# HDMI_out.net
KiCad netlist of a schematic drawn in Altium Designer
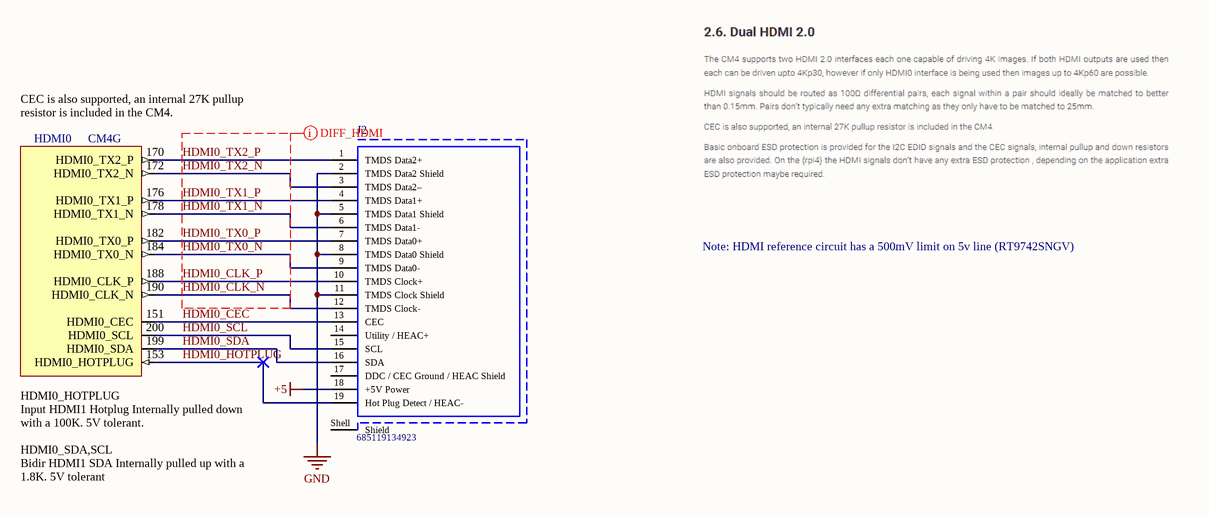
[diagram p0: HDMI out.SchDoc]

(export (version "E")
  (design (tool "Eeschema 10.0.6"))
  (components
    (comp (ref "CM4")
      (value "Raspberry Pi Compute Module 4")
      (footprint "CM4-F40C-100DS-0.4v_1.5mm_0mm")
      (description "Raspberry Pi Compute Module 4 by Amornthep Phunsin")
      (libsource (lib "CM4") (part "CM4"))
    )
    (comp (ref "J2")
      (value "685119134923")
      (footprint "685119134923")
      (description "HDMI Type A Receptacle WR-HDMI, Horizontal, SMT")
      (fields (field (name "MANUFACTURER") "Wurth Elektronik") (field (name "PUBLISHER") "WurthElektronik"))
      (libsource (lib "Altium Content Vault") (part "WE-CN-1P-1F-HD19"))
    )
  )
  (nets
    (net (code "1") (name "+5") (class "Default")
      (node (ref "J2") (pin "18") (pinfunction "+5V_Power_18") (pintype "passive"))
    )
    (net (code "2") (name "/HDMI0_CEC") (class "Default")
      (node (ref "CM4") (pin "151") (pinfunction "HDMI0_CEC_151") (pintype "open_collector"))
      (node (ref "J2") (pin "13") (pinfunction "CEC_13") (pintype "passive"))
    )
    (net (code "3") (name "/HDMI0_CLK_N") (class "Default")
      (node (ref "CM4") (pin "190") (pinfunction "HDMI0_CLK_N_190") (pintype "output"))
      (node (ref "J2") (pin "12") (pinfunction "TMDS_Clock-_12") (pintype "passive"))
    )
    (net (code "4") (name "/HDMI0_CLK_P") (class "Default")
      (node (ref "CM4") (pin "188") (pinfunction "HDMI0_CLK_P_188") (pintype "output"))
      (node (ref "J2") (pin "10") (pinfunction "TMDS_Clock+_10") (pintype "passive"))
    )
    (net (code "5") (name "/HDMI0_HOTPLUG") (class "Default")
      (node (ref "CM4") (pin "153") (pinfunction "HDMI0_HOTPLUG_153") (pintype "input"))
      (node (ref "J2") (pin "19") (pinfunction "Hot_Plug_Detect_/_HEAC-_19") (pintype "passive"))
    )
    (net (code "6") (name "/HDMI0_SCL") (class "Default")
      (node (ref "CM4") (pin "200") (pinfunction "HDMI0_SCL_200") (pintype "open_collector"))
      (node (ref "J2") (pin "15") (pinfunction "SCL_15") (pintype "passive"))
    )
    (net (code "7") (name "/HDMI0_SDA") (class "Default")
      (node (ref "CM4") (pin "199") (pinfunction "HDMI0_SDA_199") (pintype "bidirectional"))
      (node (ref "J2") (pin "16") (pinfunction "SDA_16") (pintype "passive"))
    )
    (net (code "8") (name "/HDMI0_TX0_N") (class "Default")
      (node (ref "CM4") (pin "184") (pinfunction "HDMI0_TX0_N_184") (pintype "output"))
      (node (ref "J2") (pin "9") (pinfunction "TMDS_Data0-_9") (pintype "passive"))
    )
    (net (code "9") (name "/HDMI0_TX0_P") (class "Default")
      (node (ref "CM4") (pin "182") (pinfunction "HDMI0_TX0_P_182") (pintype "output"))
      (node (ref "J2") (pin "7") (pinfunction "TMDS_Data0+_7") (pintype "passive"))
    )
    (net (code "10") (name "/HDMI0_TX1_N") (class "Default")
      (node (ref "CM4") (pin "178") (pinfunction "HDMI0_TX1_N_178") (pintype "output"))
      (node (ref "J2") (pin "6") (pinfunction "TMDS_Data1-_6") (pintype "passive"))
    )
    (net (code "11") (name "/HDMI0_TX1_P") (class "Default")
      (node (ref "CM4") (pin "176") (pinfunction "HDMI0_TX1_P_176") (pintype "output"))
      (node (ref "J2") (pin "4") (pinfunction "TMDS_Data1+_4") (pintype "passive"))
    )
    (net (code "12") (name "/HDMI0_TX2_N") (class "Default")
      (node (ref "CM4") (pin "172") (pinfunction "HDMI0_TX2_N_172") (pintype "output"))
      (node (ref "J2") (pin "3") (pinfunction "TMDS_Data2–_3") (pintype "passive"))
    )
    (net (code "13") (name "/HDMI0_TX2_P") (class "Default")
      (node (ref "CM4") (pin "170") (pinfunction "HDMI0_TX2_P_170") (pintype "output"))
      (node (ref "J2") (pin "1") (pinfunction "TMDS_Data2+_1") (pintype "passive"))
    )
    (net (code "14") (name "GND") (class "Default")
      (node (ref "J2") (pin "11") (pinfunction "TMDS_Clock_Shield_11") (pintype "passive"))
      (node (ref "J2") (pin "2") (pinfunction "TMDS_Data2_Shield_2") (pintype "passive"))
      (node (ref "J2") (pin "5") (pinfunction "TMDS_Data1_Shield_5") (pintype "passive"))
      (node (ref "J2") (pin "8") (pinfunction "TMDS_Data0_Shield_8") (pintype "passive"))
    )
    (net (code "15") (name "unconnected-(J2-DDC_{slash}_CEC_Ground_{slash}_HEAC_Shield-Pad17)") (class "Default")
      (node (ref "J2") (pin "17") (pinfunction "DDC_/_CEC_Ground_/_HEAC_Shield_17") (pintype "passive"))
    )
    (net (code "16") (name "unconnected-(J2-Shield-PadShell)") (class "Default")
      (node (ref "J2") (pin "Shell") (pinfunction "Shield_Shell") (pintype "passive"))
    )
    (net (code "17") (name "unconnected-(J2-Utility_{slash}_HEAC+-Pad14)") (class "Default")
      (node (ref "J2") (pin "14") (pinfunction "Utility_/_HEAC+_14") (pintype "passive"))
    )
  )
)
